# PL9823-breakout-board.net
KiCad netlist of a schematic drawn in EAGLE
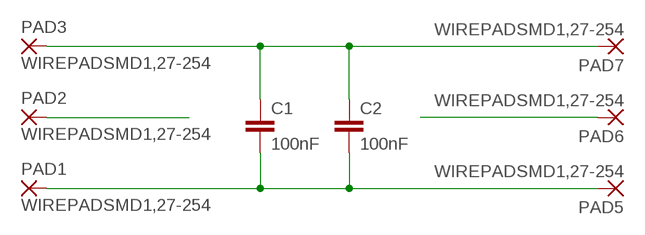
[diagram p0: schematic, sheet 1]

(export (version "E")
  (design (tool "Eeschema 10.0.6"))
  (components
    (comp (ref "C1")
      (value "100nF")
      (footprint "eagle-import:C0805K")
      (libsource (lib "eagle-import") (part "C-EUC0805K"))
    )
    (comp (ref "C2")
      (value "100nF")
      (footprint "eagle-import:C0805K")
      (libsource (lib "eagle-import") (part "C-EUC0805K"))
    )
    (comp (ref "PAD1")
      (value "WIREPADSMD1,27-254")
      (footprint "eagle-import:SMD1,27-2,54")
      (libsource (lib "eagle-import") (part "WIREPADSMD1,27-254"))
    )
    (comp (ref "PAD2")
      (value "WIREPADSMD1,27-254")
      (footprint "eagle-import:SMD1,27-2,54")
      (libsource (lib "eagle-import") (part "WIREPADSMD1,27-254"))
    )
    (comp (ref "PAD3")
      (value "WIREPADSMD1,27-254")
      (footprint "eagle-import:SMD1,27-2,54")
      (libsource (lib "eagle-import") (part "WIREPADSMD1,27-254"))
    )
    (comp (ref "PAD5")
      (value "WIREPADSMD1,27-254")
      (footprint "eagle-import:SMD1,27-2,54")
      (libsource (lib "eagle-import") (part "WIREPADSMD1,27-254"))
    )
    (comp (ref "PAD6")
      (value "WIREPADSMD1,27-254")
      (footprint "eagle-import:SMD1,27-2,54")
      (libsource (lib "eagle-import") (part "WIREPADSMD1,27-254"))
    )
    (comp (ref "PAD7")
      (value "WIREPADSMD1,27-254")
      (footprint "eagle-import:SMD1,27-2,54")
      (libsource (lib "eagle-import") (part "WIREPADSMD1,27-254"))
    )
  )
  (nets
    (net (code "1") (name "Net-(PAD1-P)") (class "Default")
      (node (ref "C1") (pin "2") (pinfunction "2_2") (pintype "passive"))
      (node (ref "C2") (pin "2") (pinfunction "2_2") (pintype "passive"))
      (node (ref "PAD1") (pin "1") (pinfunction "P_1") (pintype "passive"))
      (node (ref "PAD5") (pin "1") (pinfunction "P_1") (pintype "passive"))
    )
    (net (code "2") (name "Net-(PAD3-P)") (class "Default")
      (node (ref "C1") (pin "1") (pinfunction "1_1") (pintype "passive"))
      (node (ref "C2") (pin "1") (pinfunction "1_1") (pintype "passive"))
      (node (ref "PAD3") (pin "1") (pinfunction "P_1") (pintype "passive"))
      (node (ref "PAD7") (pin "1") (pinfunction "P_1") (pintype "passive"))
    )
    (net (code "3") (name "unconnected-(PAD2-P-Pad1)") (class "Default")
      (node (ref "PAD2") (pin "1") (pinfunction "P_1") (pintype "passive"))
    )
    (net (code "4") (name "unconnected-(PAD6-P-Pad1)") (class "Default")
      (node (ref "PAD6") (pin "1") (pinfunction "P_1") (pintype "passive"))
    )
  )
)
